# SilentStepStick-TMC5160_v15.net
KiCad netlist of a schematic drawn in EAGLE
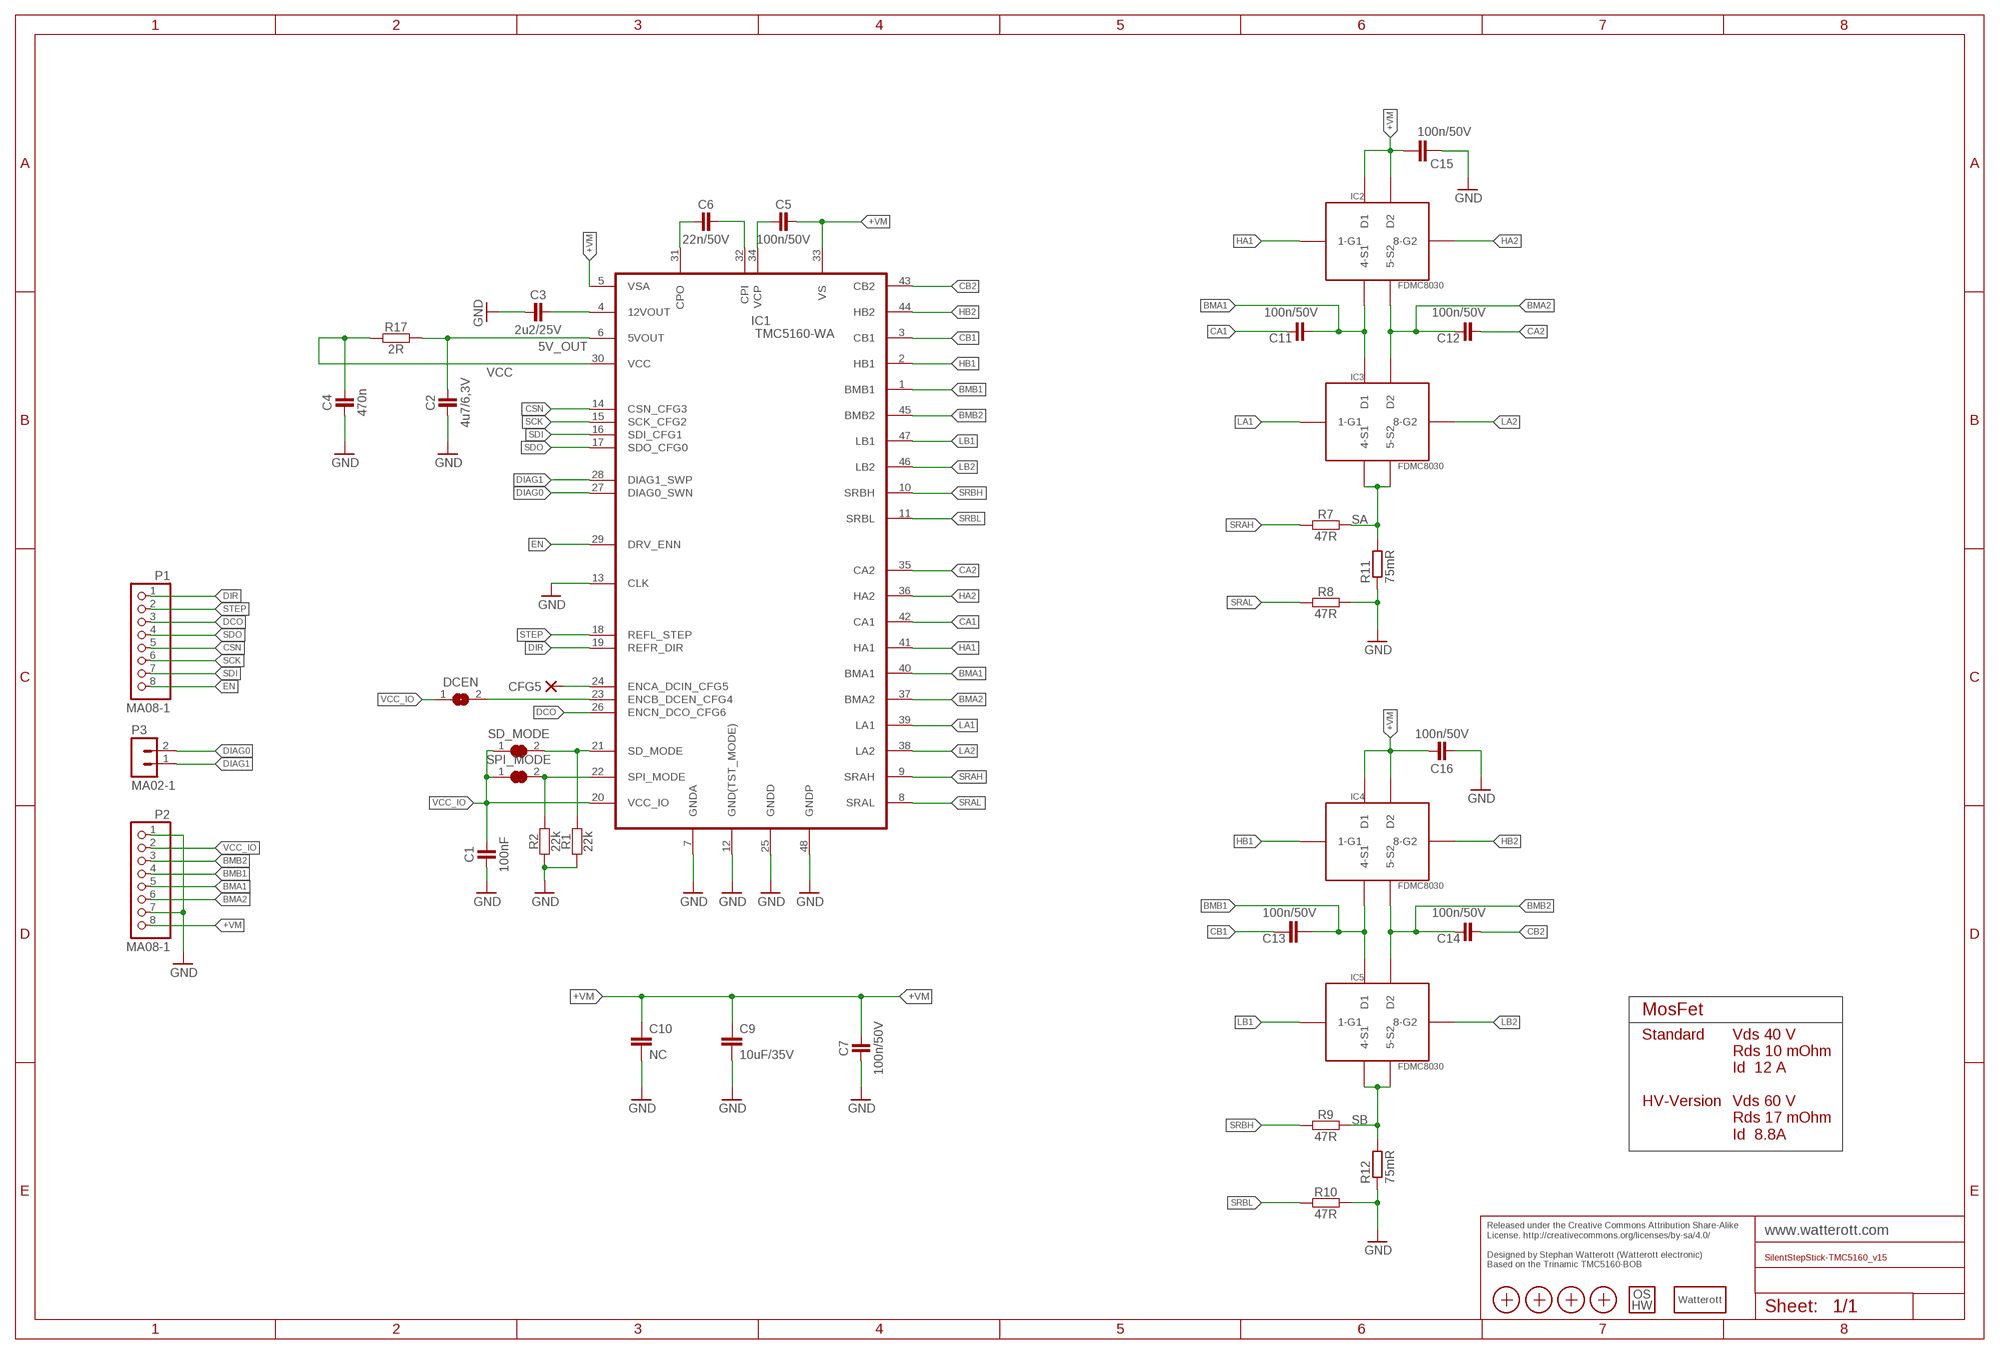
[diagram p0: schematic, sheet 1]

(export (version "E")
  (design (tool "Eeschema 10.0.6"))
  (components
    (comp (ref "C1")
      (value "100nF")
      (footprint "eagle-import:C0402")
      (libsource (lib "eagle-import") (part "CAPACITOR-0402"))
    )
    (comp (ref "C2")
      (value "4u7/6,3V")
      (footprint "eagle-import:C0402")
      (libsource (lib "eagle-import") (part "CAPACITOR-0402"))
    )
    (comp (ref "C3")
      (value "2u2/25V")
      (footprint "eagle-import:C0402")
      (libsource (lib "eagle-import") (part "CAPACITOR-0402"))
    )
    (comp (ref "C4")
      (value "470n")
      (footprint "eagle-import:C0402")
      (libsource (lib "eagle-import") (part "CAPACITOR-0402"))
    )
    (comp (ref "C5")
      (value "100n/50V")
      (footprint "eagle-import:C0402")
      (libsource (lib "eagle-import") (part "CAPACITOR-0402"))
    )
    (comp (ref "C6")
      (value "22n/50V")
      (footprint "eagle-import:C0402")
      (libsource (lib "eagle-import") (part "CAPACITOR-0402"))
    )
    (comp (ref "C7")
      (value "100n/50V")
      (footprint "eagle-import:C0402")
      (libsource (lib "eagle-import") (part "CAPACITOR-0402"))
    )
    (comp (ref "C9")
      (value "10uF/35V")
      (footprint "eagle-import:C0805")
      (libsource (lib "eagle-import") (part "C-EUC0805"))
    )
    (comp (ref "C10")
      (value "NC")
      (footprint "eagle-import:C0805")
      (libsource (lib "eagle-import") (part "C-EUC0805"))
    )
    (comp (ref "C11")
      (value "100n/50V")
      (footprint "eagle-import:C0402")
      (libsource (lib "eagle-import") (part "CAPACITOR-0402"))
    )
    (comp (ref "C12")
      (value "100n/50V")
      (footprint "eagle-import:C0402")
      (libsource (lib "eagle-import") (part "CAPACITOR-0402"))
    )
    (comp (ref "C13")
      (value "100n/50V")
      (footprint "eagle-import:C0402")
      (libsource (lib "eagle-import") (part "C-EUC0402"))
    )
    (comp (ref "C14")
      (value "100n/50V")
      (footprint "eagle-import:C0402")
      (libsource (lib "eagle-import") (part "CAPACITOR-0402"))
    )
    (comp (ref "C15")
      (value "100n/50V")
      (footprint "eagle-import:C0402")
      (libsource (lib "eagle-import") (part "C-EUC0402"))
    )
    (comp (ref "C16")
      (value "100n/50V")
      (footprint "eagle-import:C0402")
      (libsource (lib "eagle-import") (part "CAPACITOR-0402"))
    )
    (comp (ref "CFG5")
      (value "PAD-0.7_NC")
      (footprint "eagle-import:PAD-0.7_NC")
      (libsource (lib "eagle-import") (part "PAD-0.7_NC"))
    )
    (comp (ref "DCEN")
      (value "JUMPER2-0402-NC")
      (footprint "eagle-import:JUMPER2-0402_NC")
      (libsource (lib "eagle-import") (part "JUMPER2-0402-NC"))
    )
    (comp (ref "IC1")
      (value "TMC5160-WA")
      (footprint "eagle-import:VQFN56(47)_8.0X8.0X0.9MM_0.5P_EP")
      (libsource (lib "eagle-import") (part "TMC5160-WA"))
    )
    (comp (ref "IC2")
      (value "FDMC8030")
      (footprint "eagle-import:8-POWERWDFN")
      (libsource (lib "eagle-import") (part "FDMC8030"))
    )
    (comp (ref "IC3")
      (value "FDMC8030")
      (footprint "eagle-import:8-POWERWDFN")
      (libsource (lib "eagle-import") (part "FDMC8030"))
    )
    (comp (ref "IC4")
      (value "FDMC8030")
      (footprint "eagle-import:8-POWERWDFN")
      (libsource (lib "eagle-import") (part "FDMC8030"))
    )
    (comp (ref "IC5")
      (value "FDMC8030")
      (footprint "eagle-import:8-POWERWDFN")
      (libsource (lib "eagle-import") (part "FDMC8030"))
    )
    (comp (ref "LOGO1")
      (value "LOGO_SPARK-2")
      (footprint "eagle-import:SPARK_2MM")
      (libsource (lib "eagle-import") (part "LOGO_SPARK-2"))
    )
    (comp (ref "LOGO2")
      (value "LOGO_OSHW-2")
      (footprint "eagle-import:OSHW_2MM")
      (libsource (lib "eagle-import") (part "LOGO_OSHW-2"))
    )
    (comp (ref "P1")
      (value "MA08-1")
      (footprint "eagle-import:1X08-S")
      (libsource (lib "eagle-import") (part "PINHD-1X08_2.54-S"))
    )
    (comp (ref "P2")
      (value "MA08-1")
      (footprint "eagle-import:1X08-S")
      (libsource (lib "eagle-import") (part "PINHD-1X08_2.54-S"))
    )
    (comp (ref "P3")
      (value "MA02-1")
      (footprint "eagle-import:MA02-1")
      (libsource (lib "eagle-import") (part "MA02-1"))
    )
    (comp (ref "R1")
      (value "22k")
      (footprint "eagle-import:C0201")
      (libsource (lib "eagle-import") (part "RESISTOR-0201"))
    )
    (comp (ref "R2")
      (value "22k")
      (footprint "eagle-import:C0201")
      (libsource (lib "eagle-import") (part "RESISTOR-0201"))
    )
    (comp (ref "R7")
      (value "47R")
      (footprint "eagle-import:C0402")
      (libsource (lib "eagle-import") (part "RESISTOR-0402"))
    )
    (comp (ref "R8")
      (value "47R")
      (footprint "eagle-import:C0402")
      (libsource (lib "eagle-import") (part "RESISTOR-0402"))
    )
    (comp (ref "R9")
      (value "47R")
      (footprint "eagle-import:C0402")
      (libsource (lib "eagle-import") (part "RESISTOR-0402"))
    )
    (comp (ref "R10")
      (value "47R")
      (footprint "eagle-import:C0402")
      (libsource (lib "eagle-import") (part "RESISTOR-0402"))
    )
    (comp (ref "R11")
      (value "75mR")
      (footprint "eagle-import:R1206")
      (libsource (lib "eagle-import") (part "R-EU_R1206"))
    )
    (comp (ref "R12")
      (value "75mR")
      (footprint "eagle-import:R1206")
      (libsource (lib "eagle-import") (part "R-EU_R1206"))
    )
    (comp (ref "R17")
      (value "2R")
      (footprint "eagle-import:C0402")
      (libsource (lib "eagle-import") (part "RESISTOR-0402"))
    )
    (comp (ref "SD_MODE")
      (value "JUMPER2-0402-NC")
      (footprint "eagle-import:JUMPER2-0402_NC")
      (libsource (lib "eagle-import") (part "JUMPER2-0402-NC"))
    )
    (comp (ref "SPI_MODE")
      (value "JUMPER2-0402-NC")
      (footprint "eagle-import:JUMPER2-0402_NC")
      (libsource (lib "eagle-import") (part "JUMPER2-0402-NC"))
    )
    (comp (ref "X1")
      (value "PASSER-04")
      (footprint "eagle-import:PASSER_04MM")
      (libsource (lib "eagle-import") (part "PASSER-04"))
    )
    (comp (ref "X2")
      (value "PASSER-04")
      (footprint "eagle-import:PASSER_04MM")
      (libsource (lib "eagle-import") (part "PASSER-04"))
    )
    (comp (ref "X3")
      (value "PASSER-04")
      (footprint "eagle-import:PASSER_04MM")
      (libsource (lib "eagle-import") (part "PASSER-04"))
    )
    (comp (ref "X4")
      (value "PASSER-04")
      (footprint "eagle-import:PASSER_04MM")
      (libsource (lib "eagle-import") (part "PASSER-04"))
    )
  )
  (nets
    (net (code "1") (name "+VM") (class "Default")
      (node (ref "C10") (pin "1") (pinfunction "1_1") (pintype "passive"))
      (node (ref "C15") (pin "2") (pinfunction "2_2") (pintype "passive"))
      (node (ref "C16") (pin "2") (pinfunction "2_2") (pintype "passive"))
      (node (ref "C5") (pin "2") (pinfunction "2_2") (pintype "passive"))
      (node (ref "C7") (pin "2") (pinfunction "2_2") (pintype "passive"))
      (node (ref "C9") (pin "1") (pinfunction "1_1") (pintype "passive"))
      (node (ref "IC1") (pin "33") (pinfunction "VS_33") (pintype "power_in"))
      (node (ref "IC1") (pin "5") (pinfunction "VSA_5") (pintype "power_in"))
      (node (ref "IC2") (pin "P$D1") (pinfunction "D1_P$D1") (pintype "bidirectional"))
      (node (ref "IC2") (pin "P$D2") (pinfunction "D2_P$D2") (pintype "bidirectional"))
      (node (ref "IC4") (pin "P$D1") (pinfunction "D1_P$D1") (pintype "bidirectional"))
      (node (ref "IC4") (pin "P$D2") (pinfunction "D2_P$D2") (pintype "bidirectional"))
      (node (ref "P2") (pin "8") (pinfunction "8_8") (pintype "passive"))
    )
    (net (code "2") (name "/5V_OUT") (class "Default")
      (node (ref "C2") (pin "2") (pinfunction "2_2") (pintype "passive"))
      (node (ref "IC1") (pin "6") (pinfunction "5VOUT_6") (pintype "bidirectional"))
      (node (ref "R17") (pin "2") (pinfunction "2_2") (pintype "passive"))
    )
    (net (code "3") (name "/SA") (class "Default")
      (node (ref "IC3") (pin "P$4") (pinfunction "4-S1_P$4") (pintype "bidirectional"))
      (node (ref "IC3") (pin "P$5") (pinfunction "5-S2_P$5") (pintype "bidirectional"))
      (node (ref "R11") (pin "2") (pinfunction "2_2") (pintype "passive"))
      (node (ref "R7") (pin "2") (pinfunction "2_2") (pintype "passive"))
    )
    (net (code "4") (name "/SB") (class "Default")
      (node (ref "IC5") (pin "P$4") (pinfunction "4-S1_P$4") (pintype "bidirectional"))
      (node (ref "IC5") (pin "P$5") (pinfunction "5-S2_P$5") (pintype "bidirectional"))
      (node (ref "R12") (pin "2") (pinfunction "2_2") (pintype "passive"))
      (node (ref "R9") (pin "2") (pinfunction "2_2") (pintype "passive"))
    )
    (net (code "5") (name "/VCC") (class "Default")
      (node (ref "C4") (pin "2") (pinfunction "2_2") (pintype "passive"))
      (node (ref "IC1") (pin "30") (pinfunction "VCC_30") (pintype "power_in"))
      (node (ref "R17") (pin "1") (pinfunction "1_1") (pintype "passive"))
    )
    (net (code "6") (name "BMA1") (class "Default")
      (node (ref "C11") (pin "1") (pinfunction "1_1") (pintype "passive"))
      (node (ref "IC1") (pin "40") (pinfunction "BMA1_40") (pintype "input"))
      (node (ref "IC2") (pin "P$4") (pinfunction "4-S1_P$4") (pintype "bidirectional"))
      (node (ref "IC3") (pin "P$D1") (pinfunction "D1_P$D1") (pintype "bidirectional"))
      (node (ref "P2") (pin "5") (pinfunction "5_5") (pintype "passive"))
    )
    (net (code "7") (name "BMA2") (class "Default")
      (node (ref "C12") (pin "2") (pinfunction "2_2") (pintype "passive"))
      (node (ref "IC1") (pin "37") (pinfunction "BMA2_37") (pintype "input"))
      (node (ref "IC2") (pin "P$5") (pinfunction "5-S2_P$5") (pintype "bidirectional"))
      (node (ref "IC3") (pin "P$D2") (pinfunction "D2_P$D2") (pintype "bidirectional"))
      (node (ref "P2") (pin "6") (pinfunction "6_6") (pintype "passive"))
    )
    (net (code "8") (name "BMB1") (class "Default")
      (node (ref "C13") (pin "1") (pinfunction "1_1") (pintype "passive"))
      (node (ref "IC1") (pin "1") (pinfunction "BMB1_1") (pintype "input"))
      (node (ref "IC4") (pin "P$4") (pinfunction "4-S1_P$4") (pintype "bidirectional"))
      (node (ref "IC5") (pin "P$D1") (pinfunction "D1_P$D1") (pintype "bidirectional"))
      (node (ref "P2") (pin "4") (pinfunction "4_4") (pintype "passive"))
    )
    (net (code "9") (name "BMB2") (class "Default")
      (node (ref "C14") (pin "2") (pinfunction "2_2") (pintype "passive"))
      (node (ref "IC1") (pin "45") (pinfunction "BMB2_45") (pintype "input"))
      (node (ref "IC4") (pin "P$5") (pinfunction "5-S2_P$5") (pintype "bidirectional"))
      (node (ref "IC5") (pin "P$D2") (pinfunction "D2_P$D2") (pintype "bidirectional"))
      (node (ref "P2") (pin "3") (pinfunction "3_3") (pintype "passive"))
    )
    (net (code "10") (name "CA1") (class "Default")
      (node (ref "C11") (pin "2") (pinfunction "2_2") (pintype "passive"))
      (node (ref "IC1") (pin "42") (pinfunction "CA1_42") (pintype "input"))
    )
    (net (code "11") (name "CA2") (class "Default")
      (node (ref "C12") (pin "1") (pinfunction "1_1") (pintype "passive"))
      (node (ref "IC1") (pin "35") (pinfunction "CA2_35") (pintype "input"))
    )
    (net (code "12") (name "CB1") (class "Default")
      (node (ref "C13") (pin "2") (pinfunction "2_2") (pintype "passive"))
      (node (ref "IC1") (pin "3") (pinfunction "CB1_3") (pintype "input"))
    )
    (net (code "13") (name "CB2") (class "Default")
      (node (ref "C14") (pin "1") (pinfunction "1_1") (pintype "passive"))
      (node (ref "IC1") (pin "43") (pinfunction "CB2_43") (pintype "input"))
    )
    (net (code "14") (name "CSN") (class "Default")
      (node (ref "IC1") (pin "14") (pinfunction "CSN_CFG3_14") (pintype "input"))
      (node (ref "P1") (pin "5") (pinfunction "5_5") (pintype "passive"))
    )
    (net (code "15") (name "DCO") (class "Default")
      (node (ref "IC1") (pin "26") (pinfunction "ENCN_DCO_CFG6_26") (pintype "bidirectional"))
      (node (ref "P1") (pin "3") (pinfunction "3_3") (pintype "passive"))
    )
    (net (code "16") (name "DIAG0") (class "Default")
      (node (ref "IC1") (pin "27") (pinfunction "DIAG0_SWN_27") (pintype "bidirectional"))
      (node (ref "P3") (pin "2") (pinfunction "2_2") (pintype "passive"))
    )
    (net (code "17") (name "DIAG1") (class "Default")
      (node (ref "IC1") (pin "28") (pinfunction "DIAG1_SWP_28") (pintype "bidirectional"))
      (node (ref "P3") (pin "1") (pinfunction "1_1") (pintype "passive"))
    )
    (net (code "18") (name "DIR") (class "Default")
      (node (ref "IC1") (pin "19") (pinfunction "REFR_DIR_19") (pintype "input"))
      (node (ref "P1") (pin "1") (pinfunction "1_1") (pintype "passive"))
    )
    (net (code "19") (name "EN") (class "Default")
      (node (ref "IC1") (pin "29") (pinfunction "DRV_ENN_29") (pintype "input"))
      (node (ref "P1") (pin "8") (pinfunction "8_8") (pintype "passive"))
    )
    (net (code "20") (name "GND") (class "Default")
      (node (ref "C1") (pin "1") (pinfunction "1_1") (pintype "passive"))
      (node (ref "C10") (pin "2") (pinfunction "2_2") (pintype "passive"))
      (node (ref "C15") (pin "1") (pinfunction "1_1") (pintype "passive"))
      (node (ref "C16") (pin "1") (pinfunction "1_1") (pintype "passive"))
      (node (ref "C2") (pin "1") (pinfunction "1_1") (pintype "passive"))
      (node (ref "C3") (pin "1") (pinfunction "1_1") (pintype "passive"))
      (node (ref "C4") (pin "1") (pinfunction "1_1") (pintype "passive"))
      (node (ref "C7") (pin "1") (pinfunction "1_1") (pintype "passive"))
      (node (ref "C9") (pin "2") (pinfunction "2_2") (pintype "passive"))
      (node (ref "IC1") (pin "12") (pinfunction "GND(TST_MODE)_12") (pintype "input"))
      (node (ref "IC1") (pin "13") (pinfunction "CLK_13") (pintype "input"))
      (node (ref "IC1") (pin "25") (pinfunction "GNDD_25") (pintype "power_in"))
      (node (ref "IC1") (pin "48") (pinfunction "GNDP_48") (pintype "power_in"))
      (node (ref "IC1") (pin "7") (pinfunction "GNDA_7") (pintype "power_in"))
      (node (ref "P2") (pin "1") (pinfunction "1_1") (pintype "passive"))
      (node (ref "P2") (pin "7") (pinfunction "7_7") (pintype "passive"))
      (node (ref "R1") (pin "1") (pinfunction "1_1") (pintype "passive"))
      (node (ref "R10") (pin "2") (pinfunction "2_2") (pintype "passive"))
      (node (ref "R11") (pin "1") (pinfunction "1_1") (pintype "passive"))
      (node (ref "R12") (pin "1") (pinfunction "1_1") (pintype "passive"))
      (node (ref "R2") (pin "1") (pinfunction "1_1") (pintype "passive"))
      (node (ref "R8") (pin "2") (pinfunction "2_2") (pintype "passive"))
    )
    (net (code "21") (name "HA1") (class "Default")
      (node (ref "IC1") (pin "41") (pinfunction "HA1_41") (pintype "output"))
      (node (ref "IC2") (pin "P$1") (pinfunction "1-G1_P$1") (pintype "bidirectional"))
    )
    (net (code "22") (name "HA2") (class "Default")
      (node (ref "IC1") (pin "36") (pinfunction "HA2_36") (pintype "output"))
      (node (ref "IC2") (pin "P$8") (pinfunction "8-G2_P$8") (pintype "bidirectional"))
    )
    (net (code "23") (name "HB1") (class "Default")
      (node (ref "IC1") (pin "2") (pinfunction "HB1_2") (pintype "output"))
      (node (ref "IC4") (pin "P$1") (pinfunction "1-G1_P$1") (pintype "bidirectional"))
    )
    (net (code "24") (name "HB2") (class "Default")
      (node (ref "IC1") (pin "44") (pinfunction "HB2_44") (pintype "output"))
      (node (ref "IC4") (pin "P$8") (pinfunction "8-G2_P$8") (pintype "bidirectional"))
    )
    (net (code "25") (name "LA1") (class "Default")
      (node (ref "IC1") (pin "39") (pinfunction "LA1_39") (pintype "output"))
      (node (ref "IC3") (pin "P$1") (pinfunction "1-G1_P$1") (pintype "bidirectional"))
    )
    (net (code "26") (name "LA2") (class "Default")
      (node (ref "IC1") (pin "38") (pinfunction "LA2_38") (pintype "output"))
      (node (ref "IC3") (pin "P$8") (pinfunction "8-G2_P$8") (pintype "bidirectional"))
    )
    (net (code "27") (name "LB1") (class "Default")
      (node (ref "IC1") (pin "47") (pinfunction "LB1_47") (pintype "output"))
      (node (ref "IC5") (pin "P$1") (pinfunction "1-G1_P$1") (pintype "bidirectional"))
    )
    (net (code "28") (name "LB2") (class "Default")
      (node (ref "IC1") (pin "46") (pinfunction "LB2_46") (pintype "output"))
      (node (ref "IC5") (pin "P$8") (pinfunction "8-G2_P$8") (pintype "bidirectional"))
    )
    (net (code "29") (name "Net-(CFG5-P)") (class "Default")
      (node (ref "CFG5") (pin "1") (pinfunction "P_1") (pintype "passive"))
      (node (ref "IC1") (pin "24") (pinfunction "ENCA_DCIN_CFG5_24") (pintype "input"))
    )
    (net (code "30") (name "Net-(IC1-12VOUT)") (class "Default")
      (node (ref "C3") (pin "2") (pinfunction "2_2") (pintype "passive"))
      (node (ref "IC1") (pin "4") (pinfunction "12VOUT_4") (pintype "bidirectional"))
    )
    (net (code "31") (name "Net-(IC1-CPI)") (class "Default")
      (node (ref "C6") (pin "2") (pinfunction "2_2") (pintype "passive"))
      (node (ref "IC1") (pin "32") (pinfunction "CPI_32") (pintype "input"))
    )
    (net (code "32") (name "Net-(IC1-CPO)") (class "Default")
      (node (ref "C6") (pin "1") (pinfunction "1_1") (pintype "passive"))
      (node (ref "IC1") (pin "31") (pinfunction "CPO_31") (pintype "input"))
    )
    (net (code "33") (name "Net-(IC1-ENCB_DCEN_CFG4)") (class "Default")
      (node (ref "DCEN") (pin "2") (pinfunction "2_2") (pintype "passive"))
      (node (ref "IC1") (pin "23") (pinfunction "ENCB_DCEN_CFG4_23") (pintype "input"))
    )
    (net (code "34") (name "Net-(IC1-SD_MODE)") (class "Default")
      (node (ref "IC1") (pin "21") (pinfunction "SD_MODE_21") (pintype "input"))
      (node (ref "R1") (pin "2") (pinfunction "2_2") (pintype "passive"))
      (node (ref "SD_MODE") (pin "2") (pinfunction "2_2") (pintype "passive"))
    )
    (net (code "35") (name "Net-(IC1-SPI_MODE)") (class "Default")
      (node (ref "IC1") (pin "22") (pinfunction "SPI_MODE_22") (pintype "input"))
      (node (ref "R2") (pin "2") (pinfunction "2_2") (pintype "passive"))
      (node (ref "SPI_MODE") (pin "2") (pinfunction "2_2") (pintype "passive"))
    )
    (net (code "36") (name "Net-(IC1-VCP)") (class "Default")
      (node (ref "C5") (pin "1") (pinfunction "1_1") (pintype "passive"))
      (node (ref "IC1") (pin "34") (pinfunction "VCP_34") (pintype "input"))
    )
    (net (code "37") (name "SCK") (class "Default")
      (node (ref "IC1") (pin "15") (pinfunction "SCK_CFG2_15") (pintype "input"))
      (node (ref "P1") (pin "6") (pinfunction "6_6") (pintype "passive"))
    )
    (net (code "38") (name "SDI") (class "Default")
      (node (ref "IC1") (pin "16") (pinfunction "SDI_CFG1_16") (pintype "input"))
      (node (ref "P1") (pin "7") (pinfunction "7_7") (pintype "passive"))
    )
    (net (code "39") (name "SDO") (class "Default")
      (node (ref "IC1") (pin "17") (pinfunction "SDO_CFG0_17") (pintype "bidirectional"))
      (node (ref "P1") (pin "4") (pinfunction "4_4") (pintype "passive"))
    )
    (net (code "40") (name "SRAH") (class "Default")
      (node (ref "IC1") (pin "9") (pinfunction "SRAH_9") (pintype "input"))
      (node (ref "R7") (pin "1") (pinfunction "1_1") (pintype "passive"))
    )
    (net (code "41") (name "SRAL") (class "Default")
      (node (ref "IC1") (pin "8") (pinfunction "SRAL_8") (pintype "input"))
      (node (ref "R8") (pin "1") (pinfunction "1_1") (pintype "passive"))
    )
    (net (code "42") (name "SRBH") (class "Default")
      (node (ref "IC1") (pin "10") (pinfunction "SRBH_10") (pintype "input"))
      (node (ref "R9") (pin "1") (pinfunction "1_1") (pintype "passive"))
    )
    (net (code "43") (name "SRBL") (class "Default")
      (node (ref "IC1") (pin "11") (pinfunction "SRBL_11") (pintype "input"))
      (node (ref "R10") (pin "1") (pinfunction "1_1") (pintype "passive"))
    )
    (net (code "44") (name "STEP") (class "Default")
      (node (ref "IC1") (pin "18") (pinfunction "REFL_STEP_18") (pintype "input"))
      (node (ref "P1") (pin "2") (pinfunction "2_2") (pintype "passive"))
    )
    (net (code "45") (name "VCC_IO") (class "Default")
      (node (ref "C1") (pin "2") (pinfunction "2_2") (pintype "passive"))
      (node (ref "DCEN") (pin "1") (pinfunction "1_1") (pintype "passive"))
      (node (ref "IC1") (pin "20") (pinfunction "VCC_IO_20") (pintype "power_in"))
      (node (ref "P2") (pin "2") (pinfunction "2_2") (pintype "passive"))
      (node (ref "SD_MODE") (pin "1") (pinfunction "1_1") (pintype "passive"))
      (node (ref "SPI_MODE") (pin "1") (pinfunction "1_1") (pintype "passive"))
    )
  )
)
